# flanger.net
KiCad netlist of a schematic drawn in EAGLE
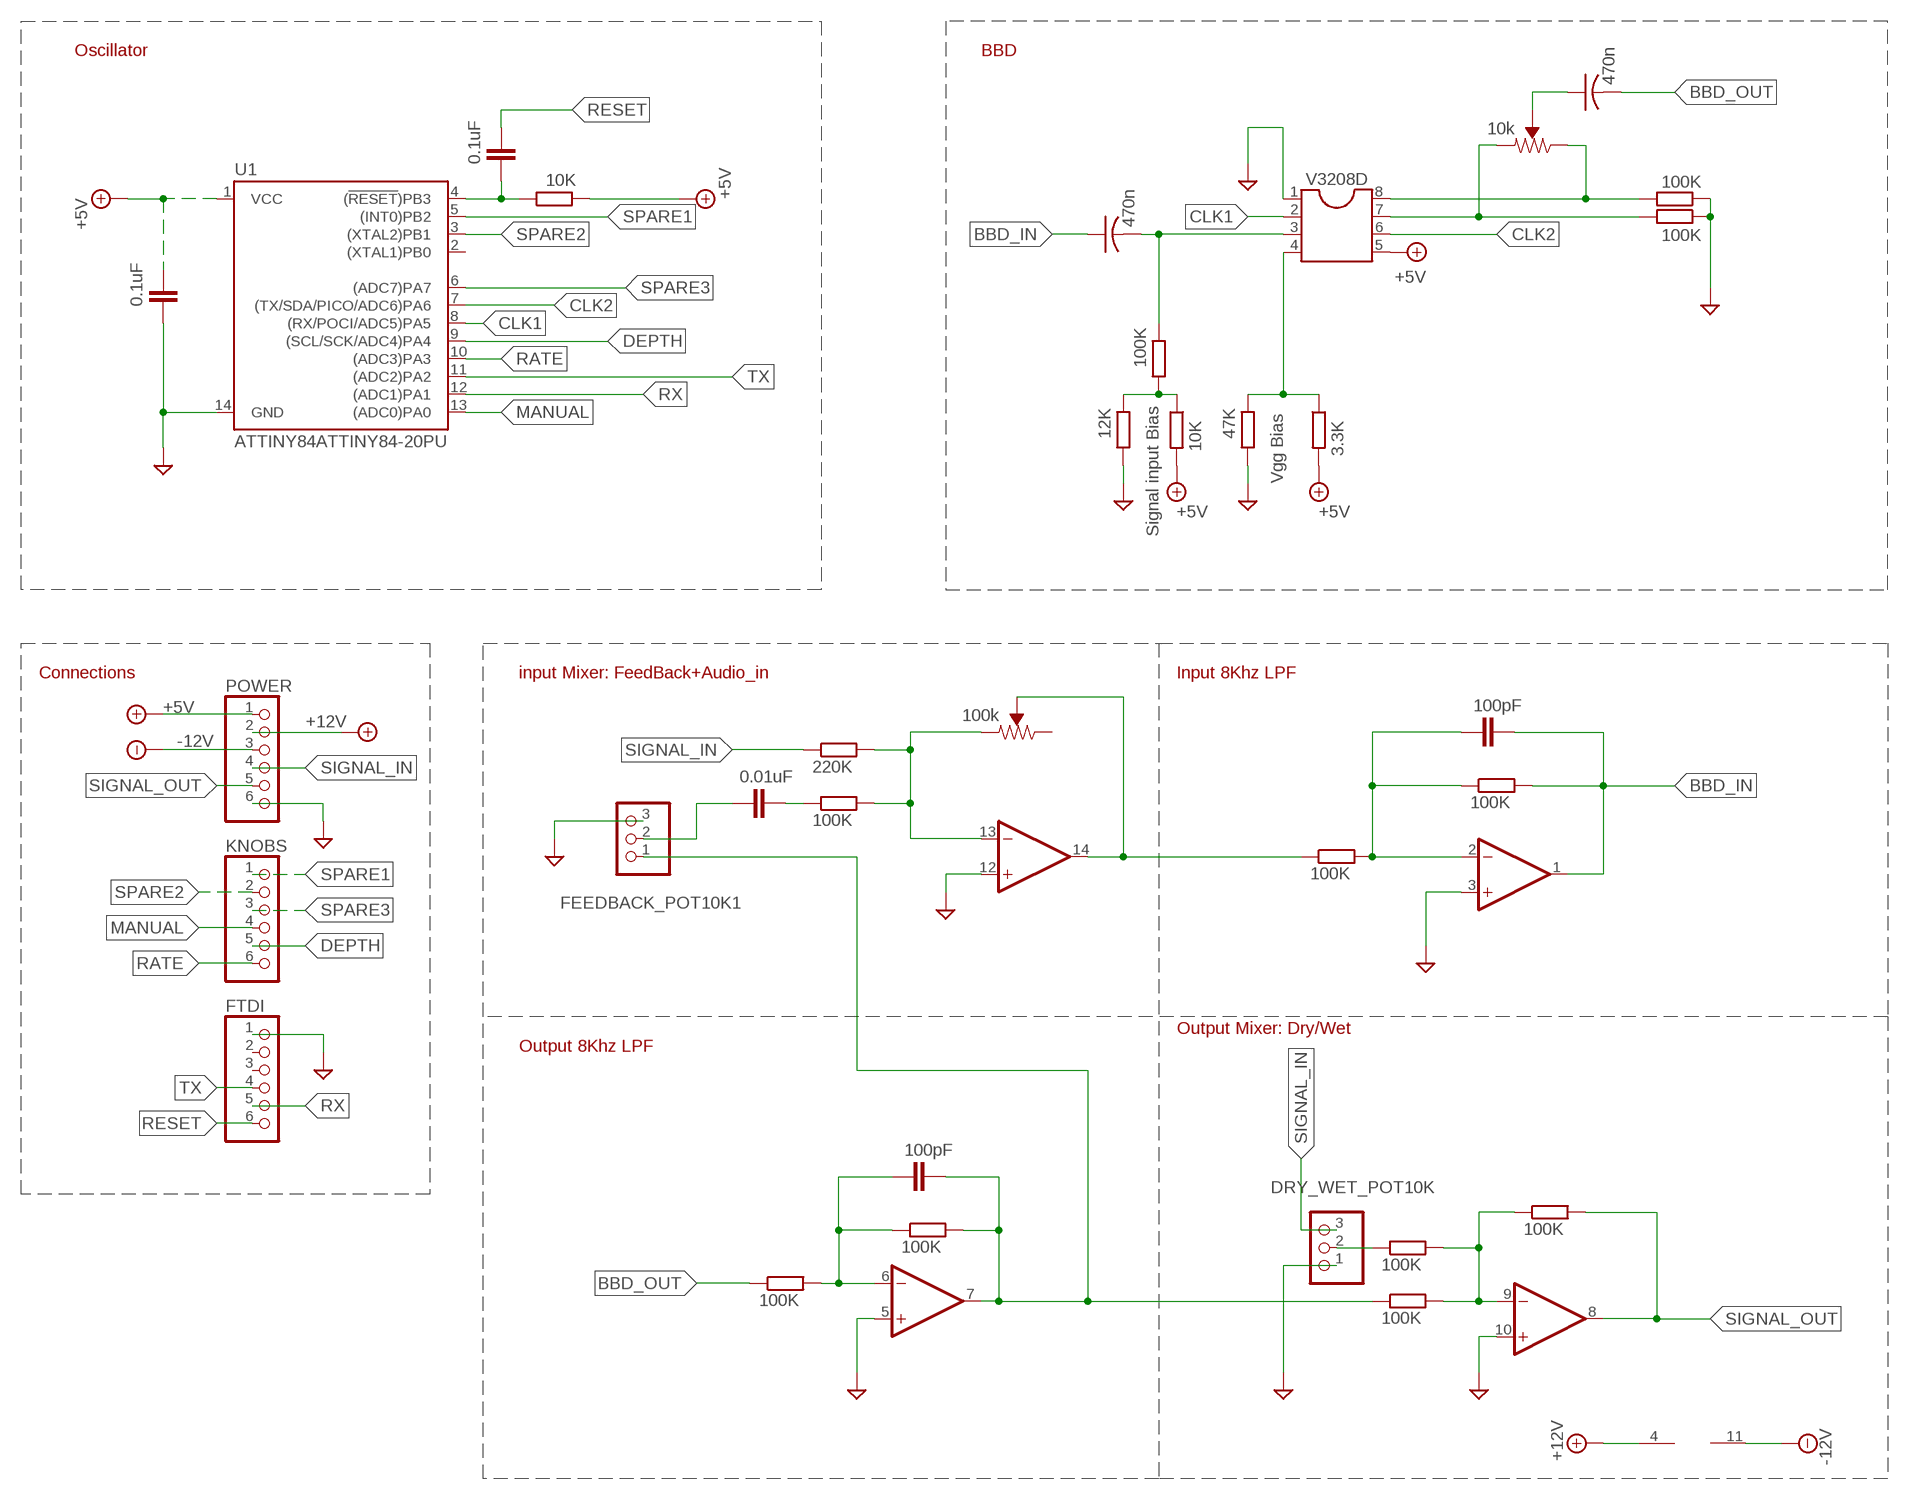
[diagram p0: schematic, sheet 1]

(export (version "E")
  (design (tool "Eeschema 10.0.6"))
  (components
    (comp (ref "C1")
      (value "470n")
      (footprint "eagle-import:C050-025X075")
      (libsource (lib "eagle-import") (part "C-US050-025X075"))
    )
    (comp (ref "C2")
      (value "470n")
      (footprint "eagle-import:C050-025X075")
      (libsource (lib "eagle-import") (part "C-US050-025X075"))
    )
    (comp (ref "C3")
      (value "100pF")
      (footprint "eagle-import:C5B2.5")
      (libsource (lib "eagle-import") (part "C5/2.5"))
    )
    (comp (ref "C4")
      (value "100pF")
      (footprint "eagle-import:C5B2.5")
      (libsource (lib "eagle-import") (part "C5/2.5"))
    )
    (comp (ref "C5")
      (value "0.01uF")
      (footprint "eagle-import:C5B2.5")
      (libsource (lib "eagle-import") (part "C5/2.5"))
    )
    (comp (ref "C6")
      (value "0.1uF")
      (footprint "eagle-import:C5B2.5")
      (libsource (lib "eagle-import") (part "C5/2.5"))
    )
    (comp (ref "C7")
      (value "0.1uF")
      (footprint "eagle-import:C5B2.5")
      (libsource (lib "eagle-import") (part "C5/2.5"))
    )
    (comp (ref "DRY_WET_POT10K")
      (value "PINHD-1X3")
      (footprint "eagle-import:1X03")
      (libsource (lib "eagle-import") (part "PINHD-1X3"))
    )
    (comp (ref "FEEDBACK_POT10K1")
      (value "PINHD-1X3")
      (footprint "eagle-import:1X03")
      (libsource (lib "eagle-import") (part "PINHD-1X3"))
    )
    (comp (ref "FTDI")
      (value "PINHD-1X6")
      (footprint "eagle-import:1X06")
      (libsource (lib "eagle-import") (part "PINHD-1X6"))
    )
    (comp (ref "IC1")
      (value "LM324N")
      (footprint "eagle-import:DIL14")
      (libsource (lib "eagle-import") (part "LM324N"))
    )
    (comp (ref "KNOBS")
      (value "PINHD-1X6")
      (footprint "eagle-import:1X06")
      (libsource (lib "eagle-import") (part "PINHD-1X6"))
    )
    (comp (ref "POWER")
      (value "PINHD-1X6")
      (footprint "eagle-import:1X06")
      (libsource (lib "eagle-import") (part "PINHD-1X6"))
    )
    (comp (ref "R1")
      (value "12K")
      (footprint "eagle-import:0207_10")
      (libsource (lib "eagle-import") (part "R-EU_0207/10"))
    )
    (comp (ref "R2")
      (value "100K")
      (footprint "eagle-import:0207_10")
      (libsource (lib "eagle-import") (part "R-EU_0207/10"))
    )
    (comp (ref "R3")
      (value "10K")
      (footprint "eagle-import:0207_10")
      (libsource (lib "eagle-import") (part "R-EU_0207/10"))
    )
    (comp (ref "R4")
      (value "47K")
      (footprint "eagle-import:0207_10")
      (libsource (lib "eagle-import") (part "R-EU_0207/10"))
    )
    (comp (ref "R5")
      (value "3.3K")
      (footprint "eagle-import:0207_10")
      (libsource (lib "eagle-import") (part "R-EU_0207/10"))
    )
    (comp (ref "R6")
      (value "100K")
      (footprint "eagle-import:0207_10")
      (libsource (lib "eagle-import") (part "R-EU_0207/10"))
    )
    (comp (ref "R7")
      (value "100K")
      (footprint "eagle-import:0207_10")
      (libsource (lib "eagle-import") (part "R-EU_0207/10"))
    )
    (comp (ref "R8")
      (value "100K")
      (footprint "eagle-import:0207_10")
      (libsource (lib "eagle-import") (part "R-EU_0207/10"))
    )
    (comp (ref "R9")
      (value "100K")
      (footprint "eagle-import:0207_10")
      (libsource (lib "eagle-import") (part "R-EU_0207/10"))
    )
    (comp (ref "R10")
      (value "100K")
      (footprint "eagle-import:0207_10")
      (libsource (lib "eagle-import") (part "R-EU_0207/10"))
    )
    (comp (ref "R11")
      (value "100K")
      (footprint "eagle-import:0207_10")
      (libsource (lib "eagle-import") (part "R-EU_0207/10"))
    )
    (comp (ref "R13")
      (value "100K")
      (footprint "eagle-import:0207_10")
      (libsource (lib "eagle-import") (part "R-EU_0207/10"))
    )
    (comp (ref "R14")
      (value "100K")
      (footprint "eagle-import:0207_10")
      (libsource (lib "eagle-import") (part "R-EU_0207/10"))
    )
    (comp (ref "R15")
      (value "220K")
      (footprint "eagle-import:0207_10")
      (libsource (lib "eagle-import") (part "R-EU_0207/10"))
    )
    (comp (ref "R16")
      (value "100K")
      (footprint "eagle-import:0207_10")
      (libsource (lib "eagle-import") (part "R-EU_0207/10"))
    )
    (comp (ref "R17")
      (value "100K")
      (footprint "eagle-import:0207_10")
      (libsource (lib "eagle-import") (part "R-EU_0207/10"))
    )
    (comp (ref "R18")
      (value "10K")
      (footprint "eagle-import:0207_10")
      (libsource (lib "eagle-import") (part "R-EU_0207/10"))
    )
    (comp (ref "U1")
      (value "ATTINY84ATTINY84-20PU")
      (footprint "eagle-import:DIP14")
      (libsource (lib "eagle-import") (part "ATTINY84ATTINY84-20PU"))
    )
    (comp (ref "V3208D")
      (value "DIL8")
      (footprint "eagle-import:DIL08")
      (libsource (lib "eagle-import") (part "DIL8"))
    )
    (comp (ref "VR1")
      (value "10k")
      (footprint "eagle-import:TRIMPOT-PTH-3386U")
      (libsource (lib "eagle-import") (part "TRIMPOT-PTH-10MM-KNOB-1/2W-10%"))
    )
    (comp (ref "VR2")
      (value "100k")
      (footprint "eagle-import:TRIMPOT-PTH-3386U")
      (libsource (lib "eagle-import") (part "TRIMPOT-PTH-10MM-KNOB-1/2W-10%"))
    )
  )
  (nets
    (net (code "1") (name "+5V") (class "Default")
      (node (ref "C6") (pin "2") (pinfunction "2_2") (pintype "passive"))
      (node (ref "POWER") (pin "1") (pinfunction "1_1") (pintype "passive"))
      (node (ref "R18") (pin "2") (pinfunction "2_2") (pintype "passive"))
      (node (ref "R3") (pin "2") (pinfunction "2_2") (pintype "passive"))
      (node (ref "R5") (pin "2") (pinfunction "2_2") (pintype "passive"))
      (node (ref "U1") (pin "1") (pinfunction "VCC_1") (pintype "bidirectional"))
      (node (ref "V3208D") (pin "5") (pinfunction "5_5") (pintype "passive"))
    )
    (net (code "2") (name "+12V") (class "Default")
      (node (ref "IC1") (pin "4") (pinfunction "V+_4") (pintype "power_in"))
      (node (ref "POWER") (pin "2") (pinfunction "2_2") (pintype "passive"))
    )
    (net (code "3") (name "-12V") (class "Default")
      (node (ref "IC1") (pin "11") (pinfunction "V-_11") (pintype "power_in"))
      (node (ref "POWER") (pin "3") (pinfunction "3_3") (pintype "passive"))
    )
    (net (code "4") (name "BBD_IN") (class "Default")
      (node (ref "C1") (pin "1") (pinfunction "1_1") (pintype "passive"))
      (node (ref "C3") (pin "2") (pinfunction "2_2") (pintype "passive"))
      (node (ref "IC1") (pin "1") (pinfunction "OUT_1") (pintype "output"))
      (node (ref "R8") (pin "2") (pinfunction "2_2") (pintype "passive"))
    )
    (net (code "5") (name "BBD_OUT") (class "Default")
      (node (ref "C2") (pin "2") (pinfunction "2_2") (pintype "passive"))
      (node (ref "R11") (pin "1") (pinfunction "1_1") (pintype "passive"))
    )
    (net (code "6") (name "CLK1") (class "Default")
      (node (ref "U1") (pin "8") (pinfunction "(RX/POCI/ADC5)PA5_8") (pintype "bidirectional"))
      (node (ref "V3208D") (pin "2") (pinfunction "2_2") (pintype "passive"))
    )
    (net (code "7") (name "CLK2") (class "Default")
      (node (ref "U1") (pin "7") (pinfunction "(TX/SDA/PICO/ADC6)PA6_7") (pintype "bidirectional"))
      (node (ref "V3208D") (pin "6") (pinfunction "6_6") (pintype "passive"))
    )
    (net (code "8") (name "DEPTH") (class "Default")
      (node (ref "KNOBS") (pin "5") (pinfunction "5_5") (pintype "passive"))
      (node (ref "U1") (pin "9") (pinfunction "(SCL/SCK/ADC4)PA4_9") (pintype "bidirectional"))
    )
    (net (code "9") (name "GND") (class "Default")
      (node (ref "C6") (pin "1") (pinfunction "1_1") (pintype "passive"))
      (node (ref "DRY_WET_POT10K") (pin "1") (pinfunction "1_1") (pintype "passive"))
      (node (ref "FEEDBACK_POT10K1") (pin "3") (pinfunction "3_3") (pintype "passive"))
      (node (ref "FTDI") (pin "1") (pinfunction "1_1") (pintype "passive"))
      (node (ref "IC1") (pin "10") (pinfunction "+IN_10") (pintype "input"))
      (node (ref "IC1") (pin "12") (pinfunction "+IN_12") (pintype "input"))
      (node (ref "IC1") (pin "3") (pinfunction "+IN_3") (pintype "input"))
      (node (ref "IC1") (pin "5") (pinfunction "+IN_5") (pintype "input"))
      (node (ref "POWER") (pin "6") (pinfunction "6_6") (pintype "passive"))
      (node (ref "R1") (pin "1") (pinfunction "1_1") (pintype "passive"))
      (node (ref "R4") (pin "1") (pinfunction "1_1") (pintype "passive"))
      (node (ref "R6") (pin "1") (pinfunction "1_1") (pintype "passive"))
      (node (ref "R7") (pin "1") (pinfunction "1_1") (pintype "passive"))
      (node (ref "U1") (pin "14") (pinfunction "GND_14") (pintype "bidirectional"))
      (node (ref "V3208D") (pin "1") (pinfunction "1_1") (pintype "passive"))
    )
    (net (code "10") (name "MANUAL") (class "Default")
      (node (ref "KNOBS") (pin "4") (pinfunction "4_4") (pintype "passive"))
      (node (ref "U1") (pin "13") (pinfunction "(ADC0)PA0_13") (pintype "bidirectional"))
    )
    (net (code "11") (name "Net-(C1-Pad2)") (class "Default")
      (node (ref "C1") (pin "2") (pinfunction "2_2") (pintype "passive"))
      (node (ref "R2") (pin "2") (pinfunction "2_2") (pintype "passive"))
      (node (ref "V3208D") (pin "3") (pinfunction "3_3") (pintype "passive"))
    )
    (net (code "12") (name "Net-(C5-Pad1)") (class "Default")
      (node (ref "C5") (pin "1") (pinfunction "1_1") (pintype "passive"))
      (node (ref "FEEDBACK_POT10K1") (pin "2") (pinfunction "2_2") (pintype "passive"))
    )
    (net (code "13") (name "Net-(C5-Pad2)") (class "Default")
      (node (ref "C5") (pin "2") (pinfunction "2_2") (pintype "passive"))
      (node (ref "R16") (pin "1") (pinfunction "1_1") (pintype "passive"))
    )
    (net (code "14") (name "Net-(DRY_WET_POT10K-Pad2)") (class "Default")
      (node (ref "DRY_WET_POT10K") (pin "2") (pinfunction "2_2") (pintype "passive"))
      (node (ref "R17") (pin "1") (pinfunction "1_1") (pintype "passive"))
    )
    (net (code "15") (name "Net-(IC1A--IN)") (class "Default")
      (node (ref "C3") (pin "1") (pinfunction "1_1") (pintype "passive"))
      (node (ref "IC1") (pin "2") (pinfunction "-IN_2") (pintype "input"))
      (node (ref "R8") (pin "1") (pinfunction "1_1") (pintype "passive"))
      (node (ref "R9") (pin "2") (pinfunction "2_2") (pintype "passive"))
    )
    (net (code "16") (name "Net-(IC1B--IN)") (class "Default")
      (node (ref "C4") (pin "1") (pinfunction "1_1") (pintype "passive"))
      (node (ref "IC1") (pin "6") (pinfunction "-IN_6") (pintype "input"))
      (node (ref "R10") (pin "1") (pinfunction "1_1") (pintype "passive"))
      (node (ref "R11") (pin "2") (pinfunction "2_2") (pintype "passive"))
    )
    (net (code "17") (name "Net-(IC1B-OUT)") (class "Default")
      (node (ref "C4") (pin "2") (pinfunction "2_2") (pintype "passive"))
      (node (ref "FEEDBACK_POT10K1") (pin "1") (pinfunction "1_1") (pintype "passive"))
      (node (ref "IC1") (pin "7") (pinfunction "OUT_7") (pintype "output"))
      (node (ref "R10") (pin "2") (pinfunction "2_2") (pintype "passive"))
      (node (ref "R14") (pin "1") (pinfunction "1_1") (pintype "passive"))
    )
    (net (code "18") (name "Net-(IC1C--IN)") (class "Default")
      (node (ref "IC1") (pin "9") (pinfunction "-IN_9") (pintype "input"))
      (node (ref "R13") (pin "1") (pinfunction "1_1") (pintype "passive"))
      (node (ref "R14") (pin "2") (pinfunction "2_2") (pintype "passive"))
      (node (ref "R17") (pin "2") (pinfunction "2_2") (pintype "passive"))
    )
    (net (code "19") (name "Net-(IC1D--IN)") (class "Default")
      (node (ref "IC1") (pin "13") (pinfunction "-IN_13") (pintype "input"))
      (node (ref "R15") (pin "2") (pinfunction "2_2") (pintype "passive"))
      (node (ref "R16") (pin "2") (pinfunction "2_2") (pintype "passive"))
      (node (ref "VR2") (pin "1") (pinfunction "CCW_1") (pintype "passive"))
    )
    (net (code "20") (name "Net-(IC1D-OUT)") (class "Default")
      (node (ref "IC1") (pin "14") (pinfunction "OUT_14") (pintype "output"))
      (node (ref "R9") (pin "1") (pinfunction "1_1") (pintype "passive"))
      (node (ref "VR2") (pin "2") (pinfunction "WIPER_2") (pintype "passive"))
    )
    (net (code "21") (name "Net-(R1-Pad2)") (class "Default")
      (node (ref "R1") (pin "2") (pinfunction "2_2") (pintype "passive"))
      (node (ref "R2") (pin "1") (pinfunction "1_1") (pintype "passive"))
      (node (ref "R3") (pin "1") (pinfunction "1_1") (pintype "passive"))
    )
    (net (code "22") (name "Net-(R4-Pad2)") (class "Default")
      (node (ref "R4") (pin "2") (pinfunction "2_2") (pintype "passive"))
      (node (ref "R5") (pin "1") (pinfunction "1_1") (pintype "passive"))
      (node (ref "V3208D") (pin "4") (pinfunction "4_4") (pintype "passive"))
    )
    (net (code "23") (name "Net-(U1-(~{RESET})PB3)") (class "Default")
      (node (ref "C7") (pin "1") (pinfunction "1_1") (pintype "passive"))
      (node (ref "R18") (pin "1") (pinfunction "1_1") (pintype "passive"))
      (node (ref "U1") (pin "4") (pinfunction "(~{RESET})PB3_4") (pintype "bidirectional"))
    )
    (net (code "24") (name "Net-(VR1-CCW)") (class "Default")
      (node (ref "R7") (pin "2") (pinfunction "2_2") (pintype "passive"))
      (node (ref "V3208D") (pin "7") (pinfunction "7_7") (pintype "passive"))
      (node (ref "VR1") (pin "1") (pinfunction "CCW_1") (pintype "passive"))
    )
    (net (code "25") (name "Net-(VR1-CW)") (class "Default")
      (node (ref "R6") (pin "2") (pinfunction "2_2") (pintype "passive"))
      (node (ref "V3208D") (pin "8") (pinfunction "8_8") (pintype "passive"))
      (node (ref "VR1") (pin "3") (pinfunction "CW_3") (pintype "passive"))
    )
    (net (code "26") (name "Net-(VR1-WIPER)") (class "Default")
      (node (ref "C2") (pin "1") (pinfunction "1_1") (pintype "passive"))
      (node (ref "VR1") (pin "2") (pinfunction "WIPER_2") (pintype "passive"))
    )
    (net (code "27") (name "RATE") (class "Default")
      (node (ref "KNOBS") (pin "6") (pinfunction "6_6") (pintype "passive"))
      (node (ref "U1") (pin "10") (pinfunction "(ADC3)PA3_10") (pintype "bidirectional"))
    )
    (net (code "28") (name "RESET") (class "Default")
      (node (ref "C7") (pin "2") (pinfunction "2_2") (pintype "passive"))
      (node (ref "FTDI") (pin "6") (pinfunction "6_6") (pintype "passive"))
    )
    (net (code "29") (name "RX") (class "Default")
      (node (ref "FTDI") (pin "5") (pinfunction "5_5") (pintype "passive"))
      (node (ref "U1") (pin "12") (pinfunction "(ADC1)PA1_12") (pintype "bidirectional"))
    )
    (net (code "30") (name "SIGNAL_IN") (class "Default")
      (node (ref "DRY_WET_POT10K") (pin "3") (pinfunction "3_3") (pintype "passive"))
      (node (ref "POWER") (pin "4") (pinfunction "4_4") (pintype "passive"))
      (node (ref "R15") (pin "1") (pinfunction "1_1") (pintype "passive"))
    )
    (net (code "31") (name "SIGNAL_OUT") (class "Default")
      (node (ref "IC1") (pin "8") (pinfunction "OUT_8") (pintype "output"))
      (node (ref "POWER") (pin "5") (pinfunction "5_5") (pintype "passive"))
      (node (ref "R13") (pin "2") (pinfunction "2_2") (pintype "passive"))
    )
    (net (code "32") (name "SPARE1") (class "Default")
      (node (ref "KNOBS") (pin "1") (pinfunction "1_1") (pintype "passive"))
      (node (ref "U1") (pin "5") (pinfunction "(INT0)PB2_5") (pintype "bidirectional"))
    )
    (net (code "33") (name "SPARE2") (class "Default")
      (node (ref "KNOBS") (pin "2") (pinfunction "2_2") (pintype "passive"))
      (node (ref "U1") (pin "3") (pinfunction "(XTAL2)PB1_3") (pintype "bidirectional"))
    )
    (net (code "34") (name "SPARE3") (class "Default")
      (node (ref "KNOBS") (pin "3") (pinfunction "3_3") (pintype "passive"))
      (node (ref "U1") (pin "6") (pinfunction "(ADC7)PA7_6") (pintype "bidirectional"))
    )
    (net (code "35") (name "TX") (class "Default")
      (node (ref "FTDI") (pin "4") (pinfunction "4_4") (pintype "passive"))
      (node (ref "U1") (pin "11") (pinfunction "(ADC2)PA2_11") (pintype "bidirectional"))
    )
    (net (code "36") (name "unconnected-(FTDI-Pad2)") (class "Default")
      (node (ref "FTDI") (pin "2") (pinfunction "2_2") (pintype "passive"))
    )
    (net (code "37") (name "unconnected-(FTDI-Pad3)") (class "Default")
      (node (ref "FTDI") (pin "3") (pinfunction "3_3") (pintype "passive"))
    )
    (net (code "38") (name "unconnected-(U1-(XTAL1)PB0-Pad2)") (class "Default")
      (node (ref "U1") (pin "2") (pinfunction "(XTAL1)PB0_2") (pintype "bidirectional"))
    )
    (net (code "39") (name "unconnected-(VR2-CW-Pad3)") (class "Default")
      (node (ref "VR2") (pin "3") (pinfunction "CW_3") (pintype "passive"))
    )
  )
)
